# capelet_solar.net
KiCad netlist of a schematic drawn in EAGLE
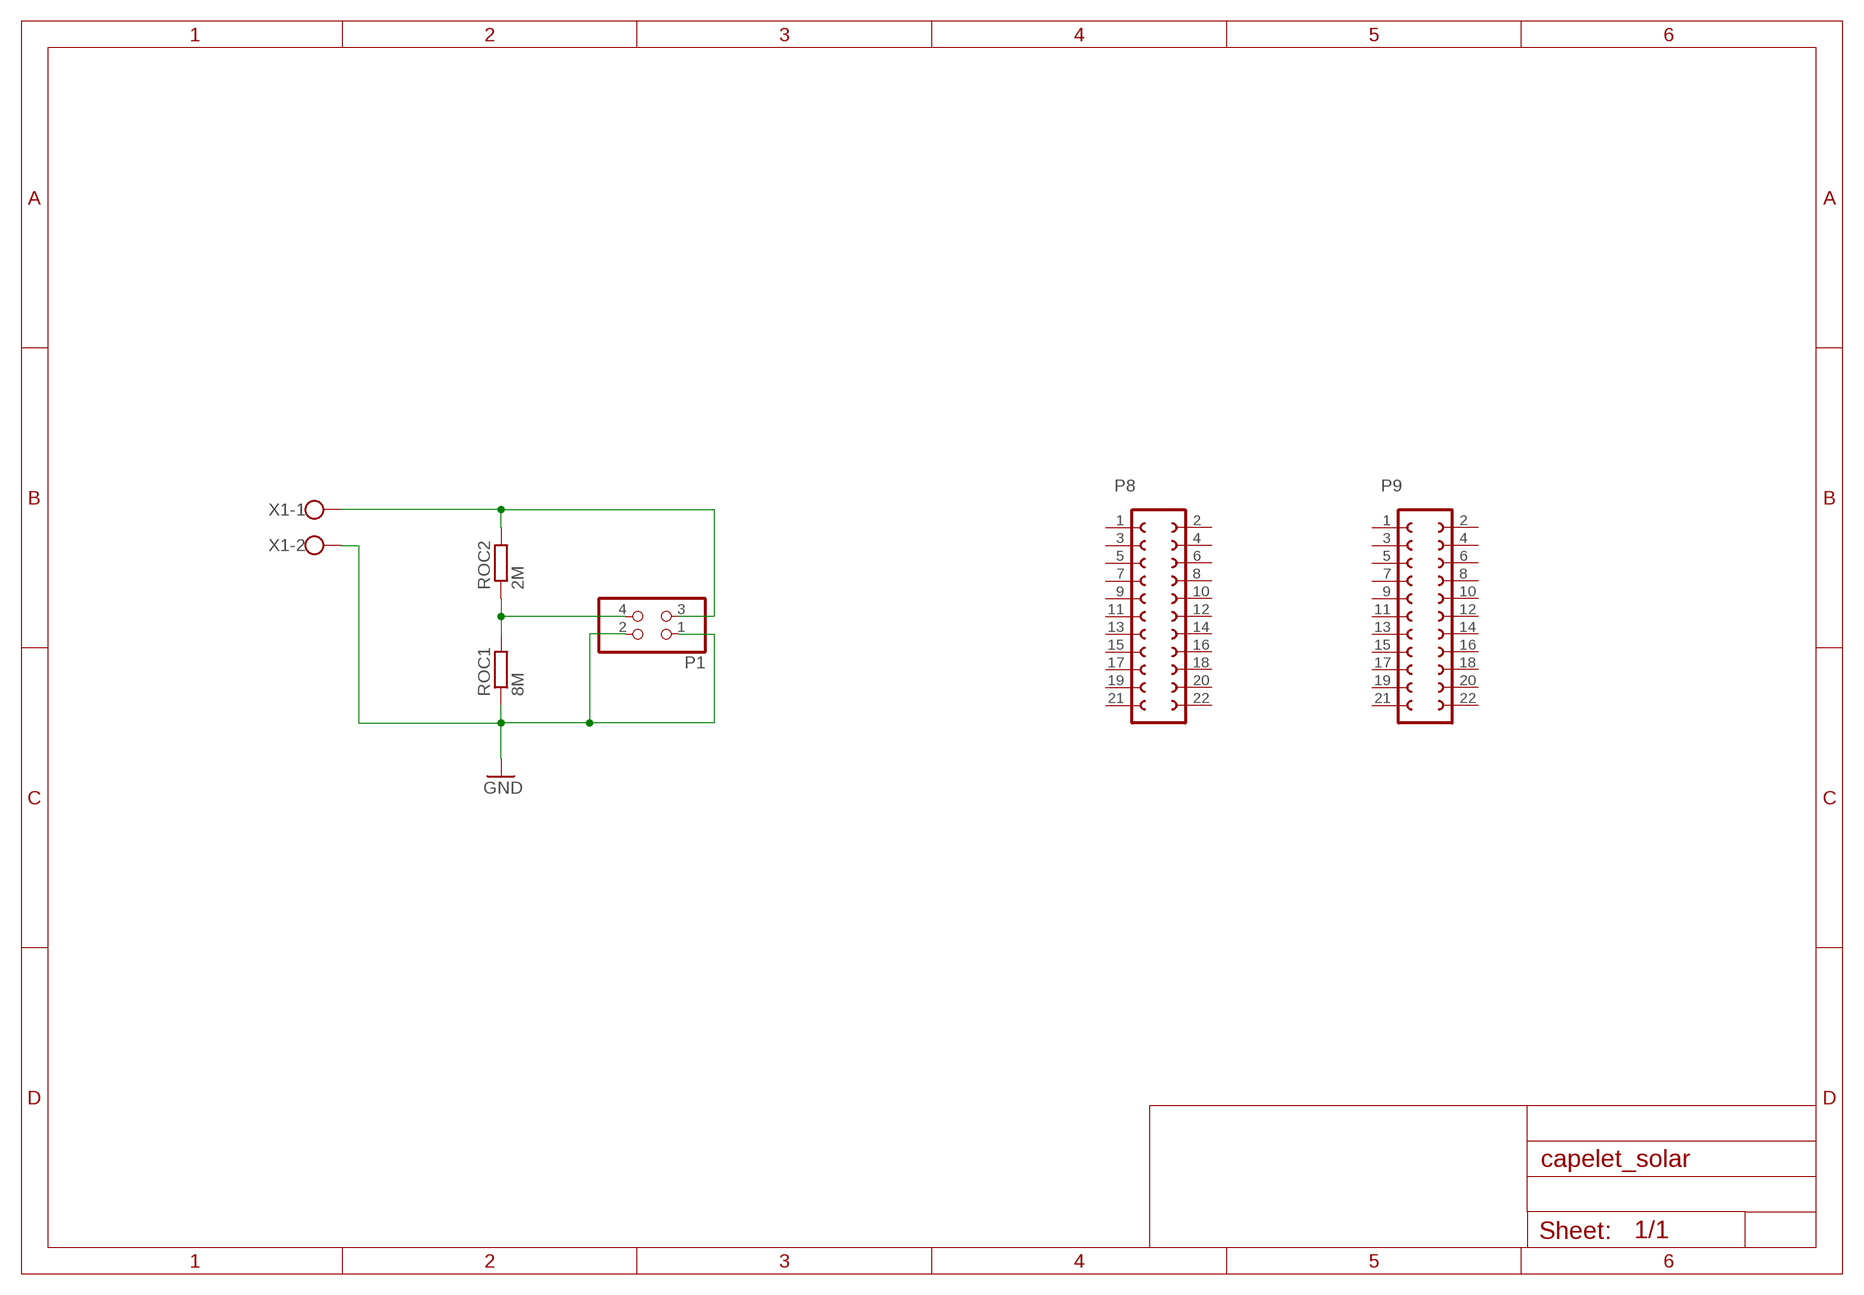
[diagram p0: schematic, sheet 1]

(export (version "E")
  (design (tool "Eeschema 10.0.6"))
  (components
    (comp (ref "P1")
      (value "PINHD-2X2")
      (footprint "eagle-import:2X02")
      (libsource (lib "eagle-import") (part "PINHD-2X2"))
    )
    (comp (ref "P8")
      (value "FE11-2")
      (footprint "eagle-import:FE11-2")
      (libsource (lib "eagle-import") (part "FE11-2"))
    )
    (comp (ref "P9")
      (value "FE11-2")
      (footprint "eagle-import:FE11-2")
      (libsource (lib "eagle-import") (part "FE11-2"))
    )
    (comp (ref "ROC1")
      (value "8M")
      (footprint "eagle-import:RESC2012X65")
      (libsource (lib "eagle-import") (part "R_SMD0805"))
    )
    (comp (ref "ROC2")
      (value "2M")
      (footprint "eagle-import:RESC2012X65")
      (libsource (lib "eagle-import") (part "R_SMD0805"))
    )
    (comp (ref "X1")
      (value "W237-102")
      (footprint "eagle-import:W237-102")
      (fields (field (name "MPN") "237-102"))
      (libsource (lib "eagle-import") (part "W237-102"))
    )
  )
  (nets
    (net (code "1") (name "GND") (class "Default")
      (node (ref "P1") (pin "1") (pinfunction "1_1") (pintype "passive"))
      (node (ref "P1") (pin "2") (pinfunction "2_2") (pintype "passive"))
      (node (ref "ROC1") (pin "1") (pinfunction "1_1") (pintype "passive"))
      (node (ref "X1") (pin "2") (pinfunction "KL_2") (pintype "passive"))
    )
    (net (code "2") (name "Net-(P1-Pad4)") (class "Default")
      (node (ref "P1") (pin "4") (pinfunction "4_4") (pintype "passive"))
      (node (ref "ROC1") (pin "2") (pinfunction "2_2") (pintype "passive"))
      (node (ref "ROC2") (pin "1") (pinfunction "1_1") (pintype "passive"))
    )
    (net (code "3") (name "Net-(X1A-KL)") (class "Default")
      (node (ref "P1") (pin "3") (pinfunction "3_3") (pintype "passive"))
      (node (ref "ROC2") (pin "2") (pinfunction "2_2") (pintype "passive"))
      (node (ref "X1") (pin "1") (pinfunction "KL_1") (pintype "passive"))
    )
    (net (code "4") (name "unconnected-(P8-25-Pad1)") (class "Default")
      (node (ref "P8") (pin "1") (pinfunction "25_1") (pintype "passive"))
    )
    (net (code "5") (name "unconnected-(P8-26-Pad2)") (class "Default")
      (node (ref "P8") (pin "2") (pinfunction "26_2") (pintype "passive"))
    )
    (net (code "6") (name "unconnected-(P8-27-Pad3)") (class "Default")
      (node (ref "P8") (pin "3") (pinfunction "27_3") (pintype "passive"))
    )
    (net (code "7") (name "unconnected-(P8-28-Pad4)") (class "Default")
      (node (ref "P8") (pin "4") (pinfunction "28_4") (pintype "passive"))
    )
    (net (code "8") (name "unconnected-(P8-29-Pad5)") (class "Default")
      (node (ref "P8") (pin "5") (pinfunction "29_5") (pintype "passive"))
    )
    (net (code "9") (name "unconnected-(P8-30-Pad6)") (class "Default")
      (node (ref "P8") (pin "6") (pinfunction "30_6") (pintype "passive"))
    )
    (net (code "10") (name "unconnected-(P8-31-Pad7)") (class "Default")
      (node (ref "P8") (pin "7") (pinfunction "31_7") (pintype "passive"))
    )
    (net (code "11") (name "unconnected-(P8-32-Pad8)") (class "Default")
      (node (ref "P8") (pin "8") (pinfunction "32_8") (pintype "passive"))
    )
    (net (code "12") (name "unconnected-(P8-33-Pad9)") (class "Default")
      (node (ref "P8") (pin "9") (pinfunction "33_9") (pintype "passive"))
    )
    (net (code "13") (name "unconnected-(P8-34-Pad10)") (class "Default")
      (node (ref "P8") (pin "10") (pinfunction "34_10") (pintype "passive"))
    )
    (net (code "14") (name "unconnected-(P8-35-Pad11)") (class "Default")
      (node (ref "P8") (pin "11") (pinfunction "35_11") (pintype "passive"))
    )
    (net (code "15") (name "unconnected-(P8-36-Pad12)") (class "Default")
      (node (ref "P8") (pin "12") (pinfunction "36_12") (pintype "passive"))
    )
    (net (code "16") (name "unconnected-(P8-37-Pad13)") (class "Default")
      (node (ref "P8") (pin "13") (pinfunction "37_13") (pintype "passive"))
    )
    (net (code "17") (name "unconnected-(P8-38-Pad14)") (class "Default")
      (node (ref "P8") (pin "14") (pinfunction "38_14") (pintype "passive"))
    )
    (net (code "18") (name "unconnected-(P8-39-Pad15)") (class "Default")
      (node (ref "P8") (pin "15") (pinfunction "39_15") (pintype "passive"))
    )
    (net (code "19") (name "unconnected-(P8-40-Pad16)") (class "Default")
      (node (ref "P8") (pin "16") (pinfunction "40_16") (pintype "passive"))
    )
    (net (code "20") (name "unconnected-(P8-41-Pad17)") (class "Default")
      (node (ref "P8") (pin "17") (pinfunction "41_17") (pintype "passive"))
    )
    (net (code "21") (name "unconnected-(P8-42-Pad18)") (class "Default")
      (node (ref "P8") (pin "18") (pinfunction "42_18") (pintype "passive"))
    )
    (net (code "22") (name "unconnected-(P8-43-Pad19)") (class "Default")
      (node (ref "P8") (pin "19") (pinfunction "43_19") (pintype "passive"))
    )
    (net (code "23") (name "unconnected-(P8-44-Pad20)") (class "Default")
      (node (ref "P8") (pin "20") (pinfunction "44_20") (pintype "passive"))
    )
    (net (code "24") (name "unconnected-(P8-45-Pad21)") (class "Default")
      (node (ref "P8") (pin "21") (pinfunction "45_21") (pintype "passive"))
    )
    (net (code "25") (name "unconnected-(P8-46-Pad22)") (class "Default")
      (node (ref "P8") (pin "22") (pinfunction "46_22") (pintype "passive"))
    )
    (net (code "26") (name "unconnected-(P9-25-Pad1)") (class "Default")
      (node (ref "P9") (pin "1") (pinfunction "25_1") (pintype "passive"))
    )
    (net (code "27") (name "unconnected-(P9-26-Pad2)") (class "Default")
      (node (ref "P9") (pin "2") (pinfunction "26_2") (pintype "passive"))
    )
    (net (code "28") (name "unconnected-(P9-27-Pad3)") (class "Default")
      (node (ref "P9") (pin "3") (pinfunction "27_3") (pintype "passive"))
    )
    (net (code "29") (name "unconnected-(P9-28-Pad4)") (class "Default")
      (node (ref "P9") (pin "4") (pinfunction "28_4") (pintype "passive"))
    )
    (net (code "30") (name "unconnected-(P9-29-Pad5)") (class "Default")
      (node (ref "P9") (pin "5") (pinfunction "29_5") (pintype "passive"))
    )
    (net (code "31") (name "unconnected-(P9-30-Pad6)") (class "Default")
      (node (ref "P9") (pin "6") (pinfunction "30_6") (pintype "passive"))
    )
    (net (code "32") (name "unconnected-(P9-31-Pad7)") (class "Default")
      (node (ref "P9") (pin "7") (pinfunction "31_7") (pintype "passive"))
    )
    (net (code "33") (name "unconnected-(P9-32-Pad8)") (class "Default")
      (node (ref "P9") (pin "8") (pinfunction "32_8") (pintype "passive"))
    )
    (net (code "34") (name "unconnected-(P9-33-Pad9)") (class "Default")
      (node (ref "P9") (pin "9") (pinfunction "33_9") (pintype "passive"))
    )
    (net (code "35") (name "unconnected-(P9-34-Pad10)") (class "Default")
      (node (ref "P9") (pin "10") (pinfunction "34_10") (pintype "passive"))
    )
    (net (code "36") (name "unconnected-(P9-35-Pad11)") (class "Default")
      (node (ref "P9") (pin "11") (pinfunction "35_11") (pintype "passive"))
    )
    (net (code "37") (name "unconnected-(P9-36-Pad12)") (class "Default")
      (node (ref "P9") (pin "12") (pinfunction "36_12") (pintype "passive"))
    )
    (net (code "38") (name "unconnected-(P9-37-Pad13)") (class "Default")
      (node (ref "P9") (pin "13") (pinfunction "37_13") (pintype "passive"))
    )
    (net (code "39") (name "unconnected-(P9-38-Pad14)") (class "Default")
      (node (ref "P9") (pin "14") (pinfunction "38_14") (pintype "passive"))
    )
    (net (code "40") (name "unconnected-(P9-39-Pad15)") (class "Default")
      (node (ref "P9") (pin "15") (pinfunction "39_15") (pintype "passive"))
    )
    (net (code "41") (name "unconnected-(P9-40-Pad16)") (class "Default")
      (node (ref "P9") (pin "16") (pinfunction "40_16") (pintype "passive"))
    )
    (net (code "42") (name "unconnected-(P9-41-Pad17)") (class "Default")
      (node (ref "P9") (pin "17") (pinfunction "41_17") (pintype "passive"))
    )
    (net (code "43") (name "unconnected-(P9-42-Pad18)") (class "Default")
      (node (ref "P9") (pin "18") (pinfunction "42_18") (pintype "passive"))
    )
    (net (code "44") (name "unconnected-(P9-43-Pad19)") (class "Default")
      (node (ref "P9") (pin "19") (pinfunction "43_19") (pintype "passive"))
    )
    (net (code "45") (name "unconnected-(P9-44-Pad20)") (class "Default")
      (node (ref "P9") (pin "20") (pinfunction "44_20") (pintype "passive"))
    )
    (net (code "46") (name "unconnected-(P9-45-Pad21)") (class "Default")
      (node (ref "P9") (pin "21") (pinfunction "45_21") (pintype "passive"))
    )
    (net (code "47") (name "unconnected-(P9-46-Pad22)") (class "Default")
      (node (ref "P9") (pin "22") (pinfunction "46_22") (pintype "passive"))
    )
  )
)
